# ton1.net
KiCad netlist of a schematic drawn in EAGLE
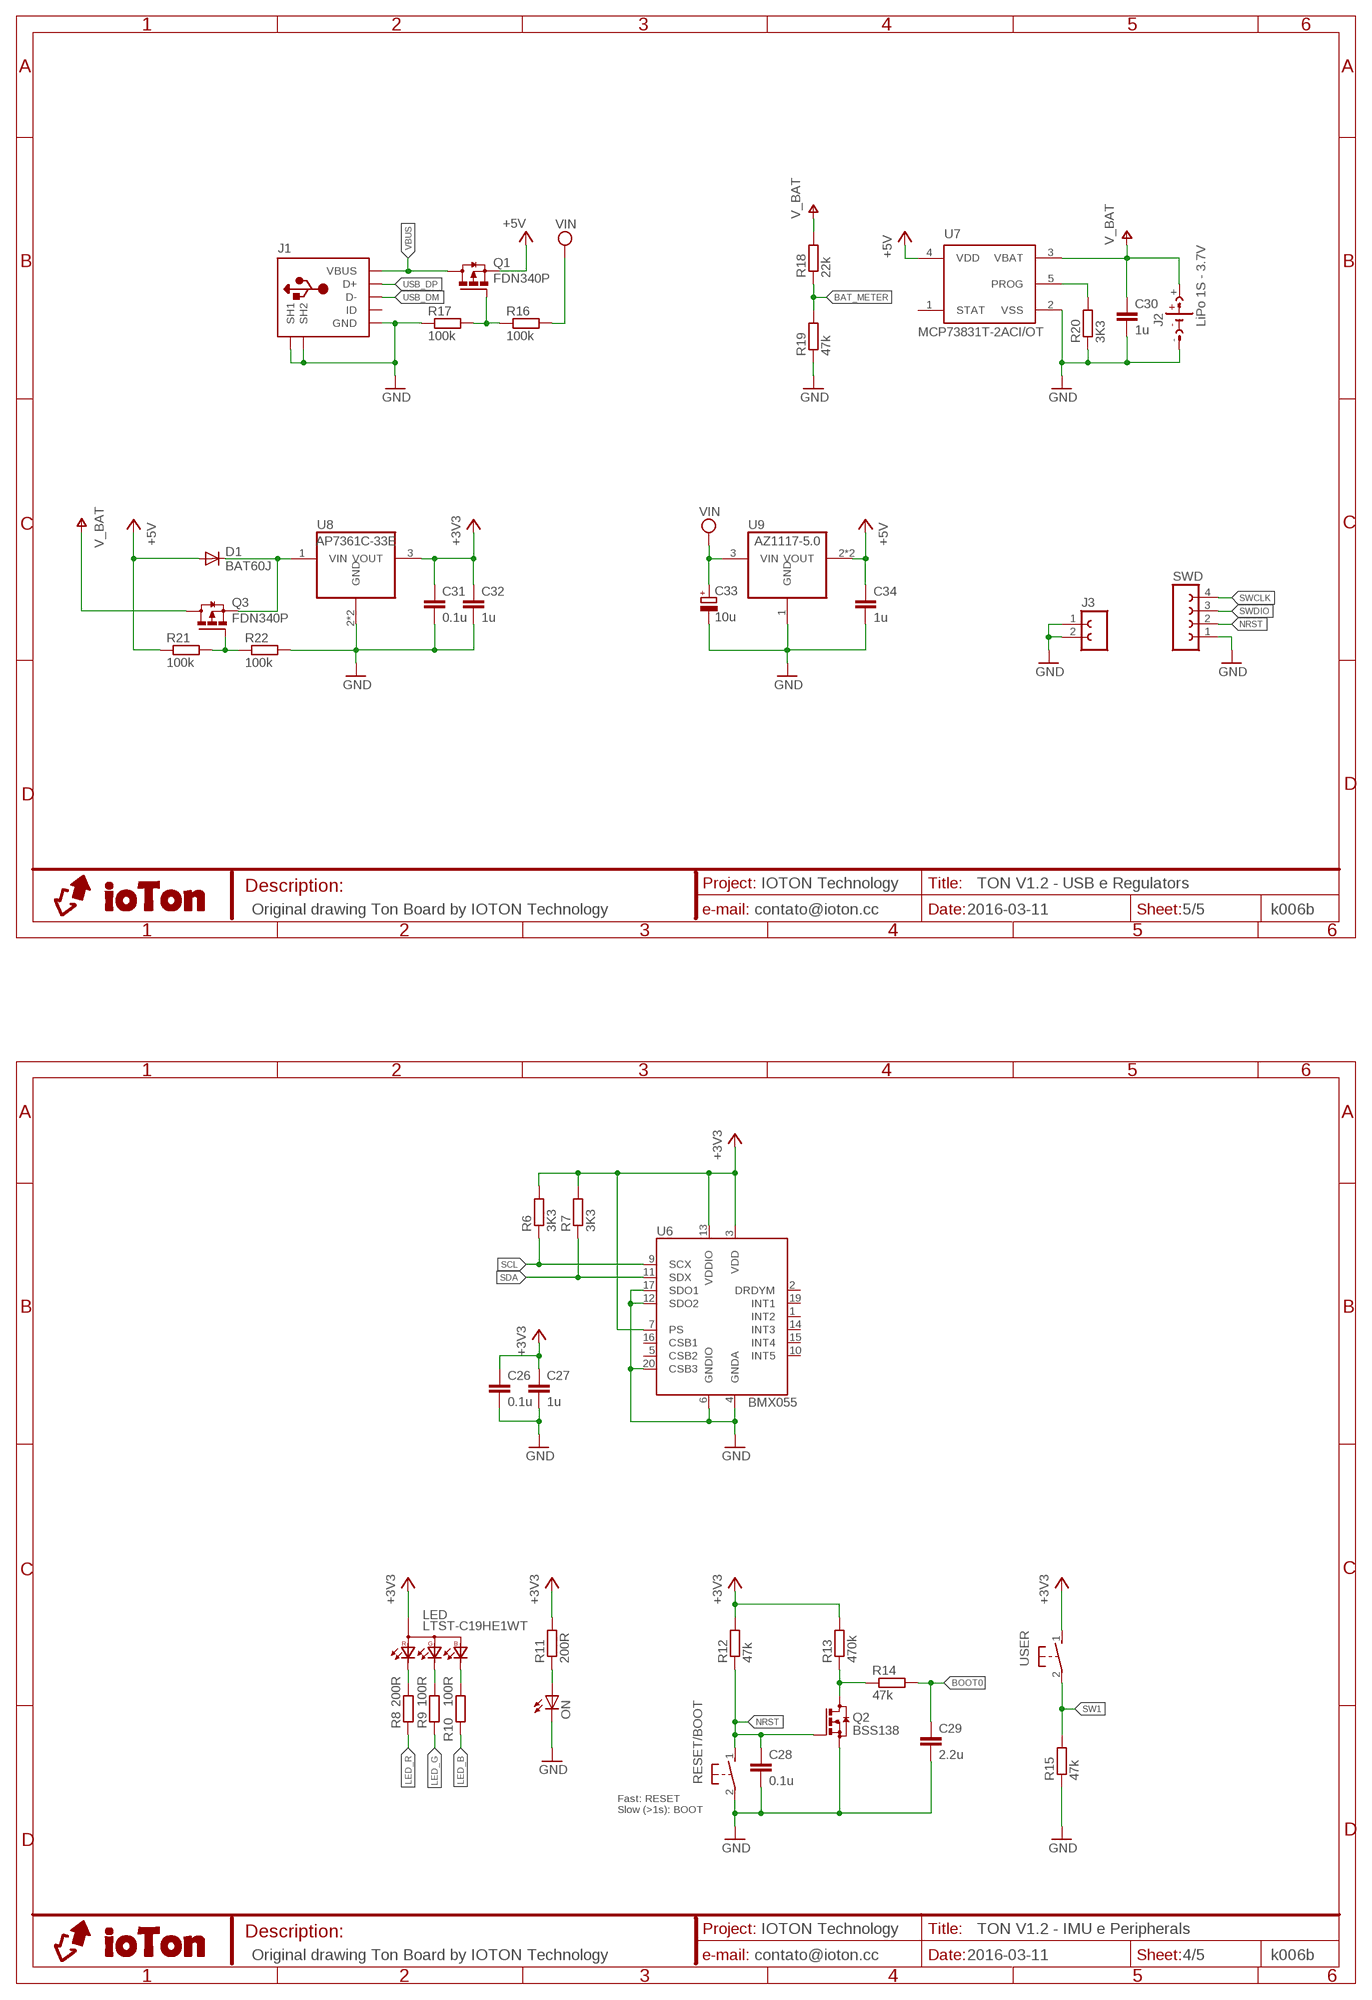
[diagram p0: schematic, sheet 1, part 1 of 3]
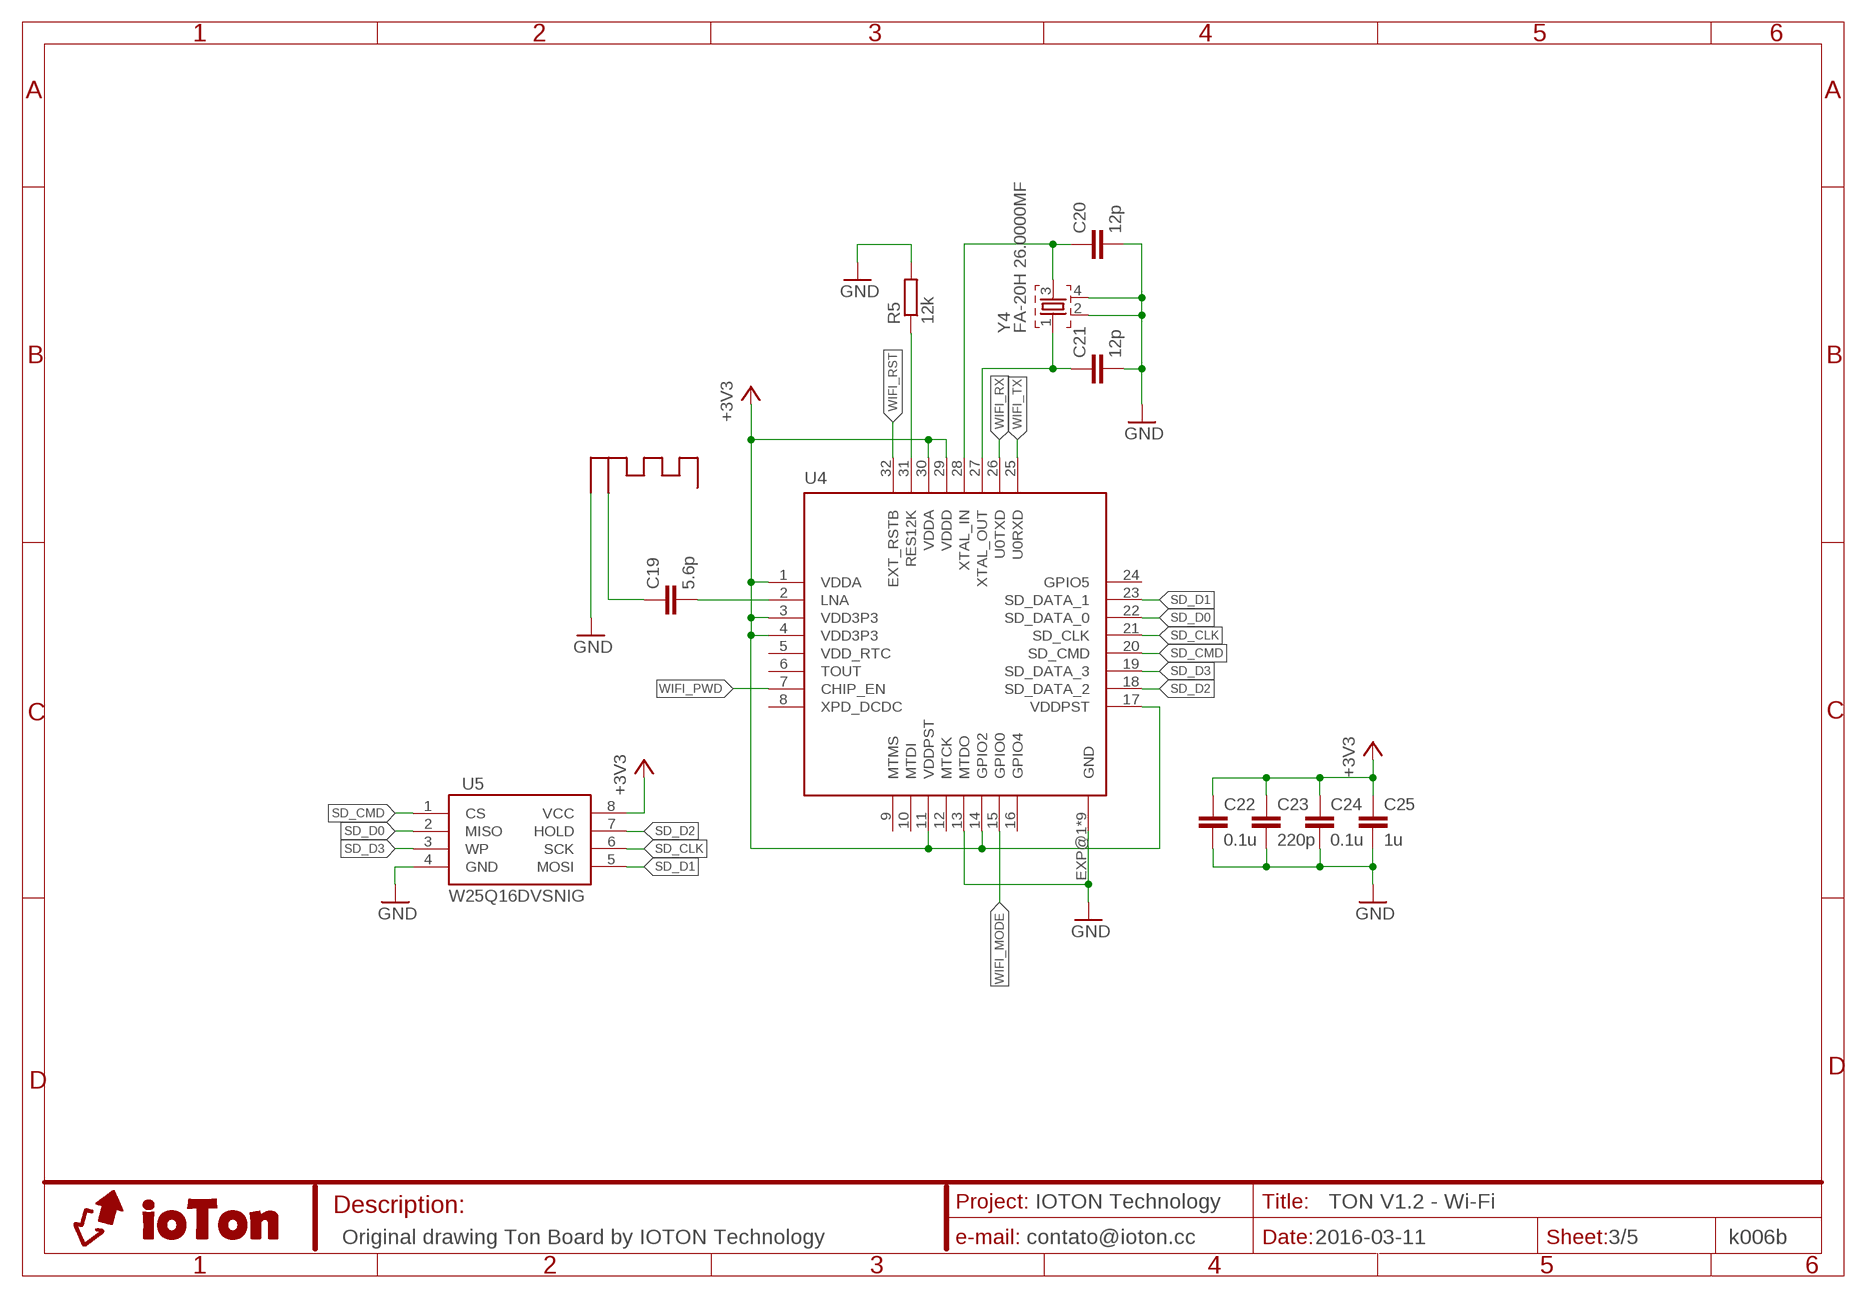
[diagram p1: schematic, sheet 1, part 2 of 3]
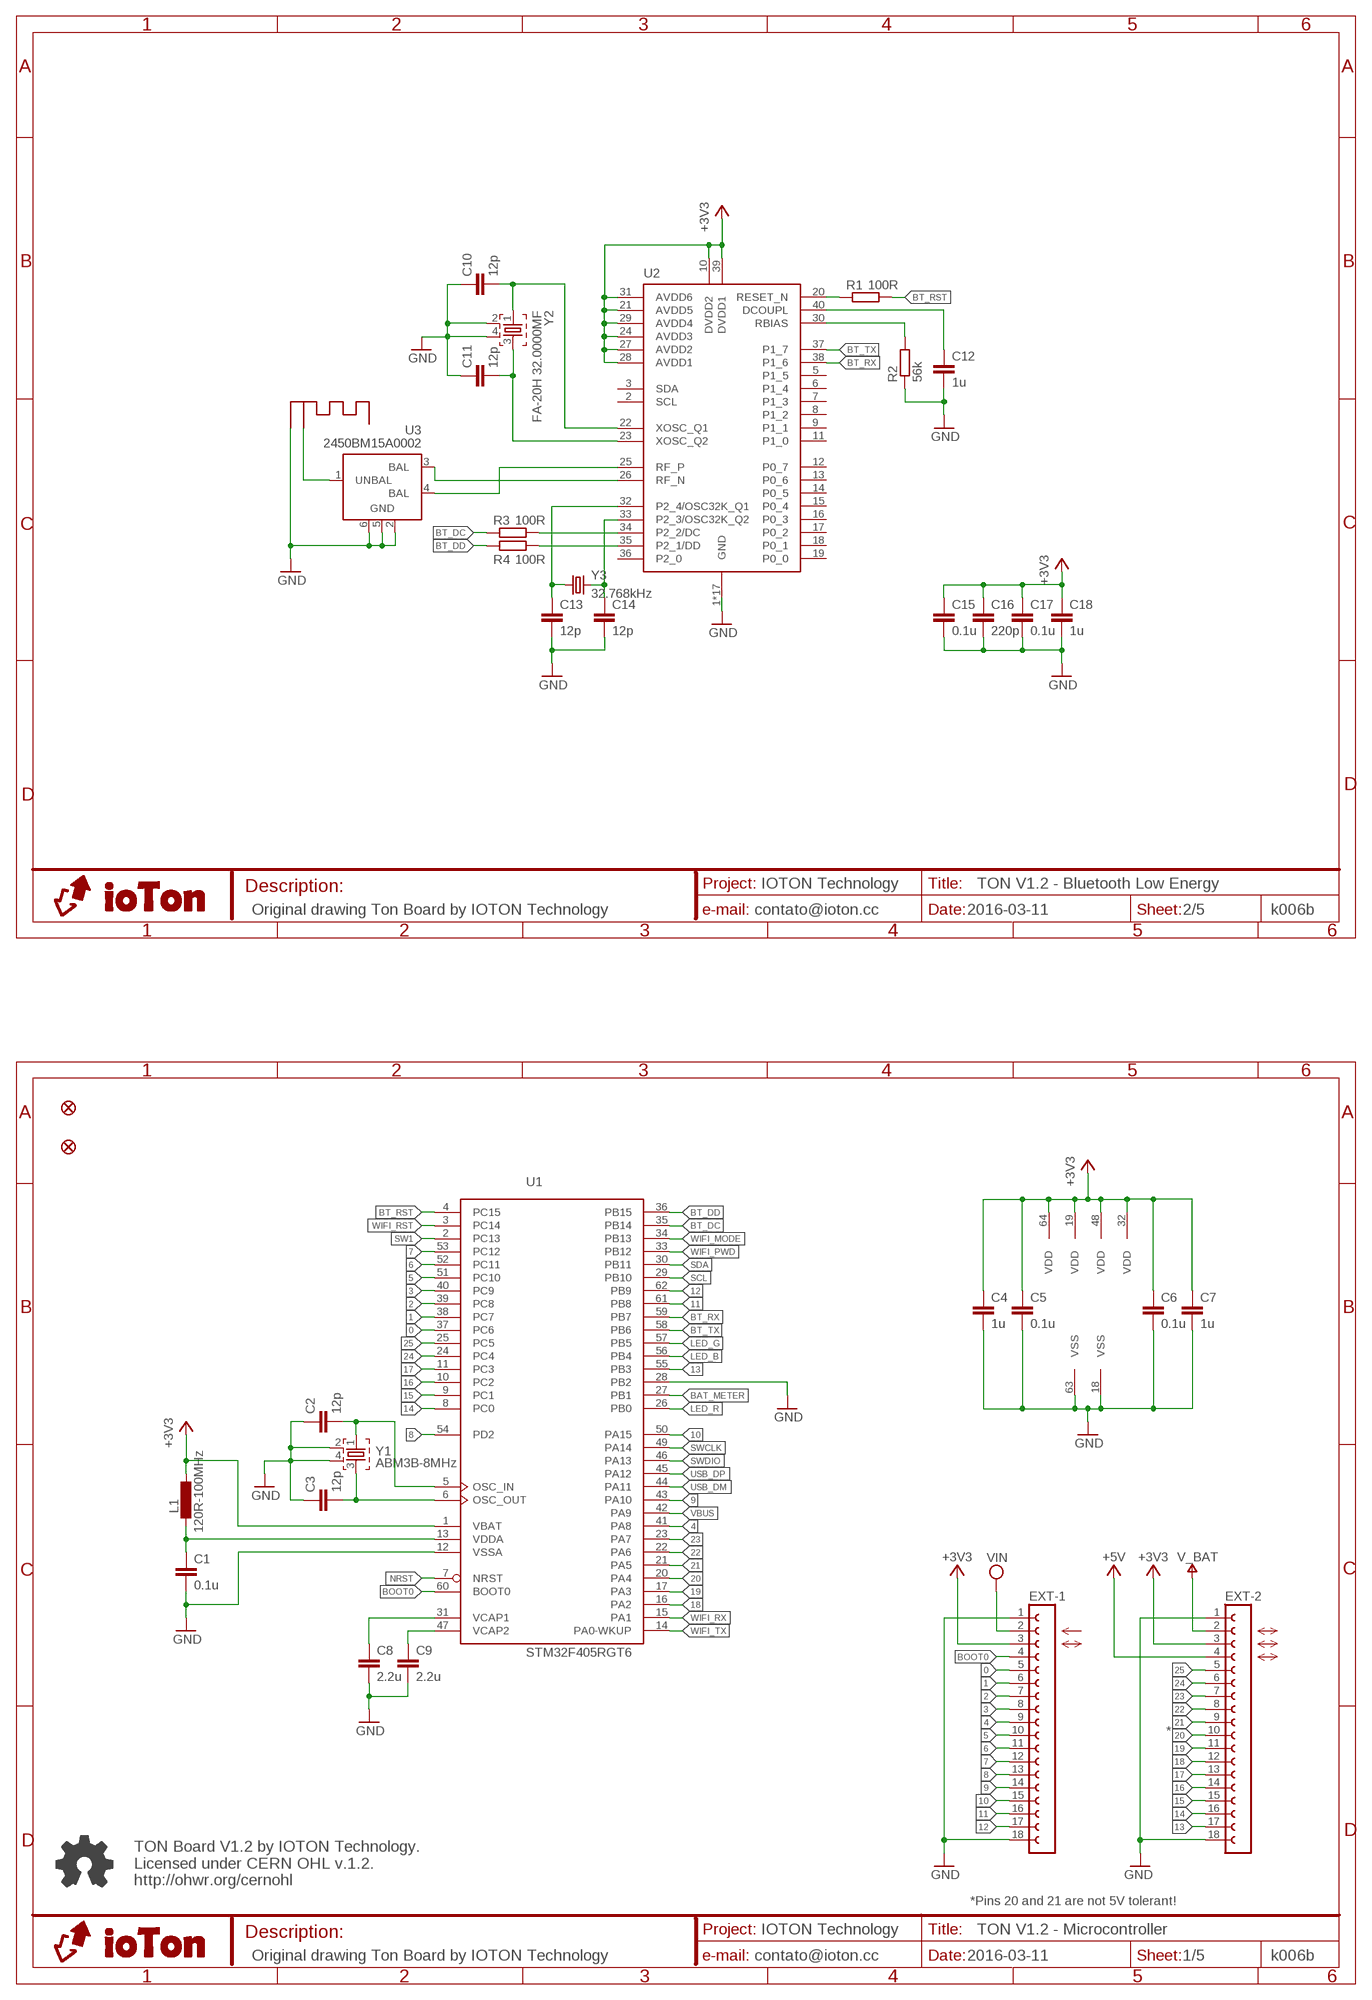
[diagram p2: schematic, sheet 1, part 3 of 3]

(export (version "E")
  (design (tool "Eeschema 10.0.6"))
  (components
    (comp (ref "C1")
      (value "0.1u")
      (footprint "eagle-import:C0603")
      (libsource (lib "eagle-import") (part "C-EUC0603"))
    )
    (comp (ref "C2")
      (value "12p")
      (footprint "eagle-import:C0402")
      (libsource (lib "eagle-import") (part "C-EUC0402"))
    )
    (comp (ref "C3")
      (value "12p")
      (footprint "eagle-import:C0402")
      (libsource (lib "eagle-import") (part "C-EUC0402"))
    )
    (comp (ref "C4")
      (value "1u")
      (footprint "eagle-import:C0603")
      (libsource (lib "eagle-import") (part "C-EUC0603"))
    )
    (comp (ref "C5")
      (value "0.1u")
      (footprint "eagle-import:C0603")
      (libsource (lib "eagle-import") (part "C-EUC0603"))
    )
    (comp (ref "C6")
      (value "0.1u")
      (footprint "eagle-import:C0603")
      (libsource (lib "eagle-import") (part "C-EUC0603"))
    )
    (comp (ref "C7")
      (value "1u")
      (footprint "eagle-import:C0603")
      (libsource (lib "eagle-import") (part "C-EUC0603"))
    )
    (comp (ref "C8")
      (value "2.2u")
      (footprint "eagle-import:C0603")
      (libsource (lib "eagle-import") (part "C-EUC0603"))
    )
    (comp (ref "C9")
      (value "2.2u")
      (footprint "eagle-import:C0603")
      (libsource (lib "eagle-import") (part "C-EUC0603"))
    )
    (comp (ref "C10")
      (value "12p")
      (footprint "eagle-import:C0402")
      (libsource (lib "eagle-import") (part "C-EUC0402"))
    )
    (comp (ref "C11")
      (value "12p")
      (footprint "eagle-import:C0402")
      (libsource (lib "eagle-import") (part "C-EUC0402"))
    )
    (comp (ref "C12")
      (value "1u")
      (footprint "eagle-import:C0402")
      (libsource (lib "eagle-import") (part "C-EUC0402"))
    )
    (comp (ref "C13")
      (value "12p")
      (footprint "eagle-import:C0402")
      (libsource (lib "eagle-import") (part "C-EUC0402"))
    )
    (comp (ref "C14")
      (value "12p")
      (footprint "eagle-import:C0402")
      (libsource (lib "eagle-import") (part "C-EUC0402"))
    )
    (comp (ref "C15")
      (value "0.1u")
      (footprint "eagle-import:C0402")
      (libsource (lib "eagle-import") (part "C-EUC0402"))
    )
    (comp (ref "C16")
      (value "220p")
      (footprint "eagle-import:C0402")
      (libsource (lib "eagle-import") (part "C-EUC0402"))
    )
    (comp (ref "C17")
      (value "0.1u")
      (footprint "eagle-import:C0402")
      (libsource (lib "eagle-import") (part "C-EUC0402"))
    )
    (comp (ref "C18")
      (value "1u")
      (footprint "eagle-import:C0402")
      (libsource (lib "eagle-import") (part "C-EUC0402"))
    )
    (comp (ref "C19")
      (value "5.6p")
      (footprint "eagle-import:C0402")
      (libsource (lib "eagle-import") (part "C-EUC0402"))
    )
    (comp (ref "C20")
      (value "12p")
      (footprint "eagle-import:C0402")
      (libsource (lib "eagle-import") (part "C-EUC0402"))
    )
    (comp (ref "C21")
      (value "12p")
      (footprint "eagle-import:C0402")
      (libsource (lib "eagle-import") (part "C-EUC0402"))
    )
    (comp (ref "C22")
      (value "0.1u")
      (footprint "eagle-import:C0402")
      (libsource (lib "eagle-import") (part "C-EUC0402"))
    )
    (comp (ref "C23")
      (value "220p")
      (footprint "eagle-import:C0402")
      (libsource (lib "eagle-import") (part "C-EUC0402"))
    )
    (comp (ref "C24")
      (value "0.1u")
      (footprint "eagle-import:C0402")
      (libsource (lib "eagle-import") (part "C-EUC0402"))
    )
    (comp (ref "C25")
      (value "1u")
      (footprint "eagle-import:C0402")
      (libsource (lib "eagle-import") (part "C-EUC0402"))
    )
    (comp (ref "C26")
      (value "0.1u")
      (footprint "eagle-import:C0603")
      (libsource (lib "eagle-import") (part "C-EUC0603"))
    )
    (comp (ref "C27")
      (value "1u")
      (footprint "eagle-import:C0603")
      (libsource (lib "eagle-import") (part "C-EUC0603"))
    )
    (comp (ref "C28")
      (value "0.1u")
      (footprint "eagle-import:C0603")
      (libsource (lib "eagle-import") (part "C-EUC0603"))
    )
    (comp (ref "C29")
      (value "2.2u")
      (footprint "eagle-import:C0603")
      (libsource (lib "eagle-import") (part "C-EUC0603"))
    )
    (comp (ref "C30")
      (value "1u")
      (footprint "eagle-import:C0603")
      (libsource (lib "eagle-import") (part "C-EUC0603"))
    )
    (comp (ref "C31")
      (value "0.1u")
      (footprint "eagle-import:C0603")
      (libsource (lib "eagle-import") (part "C-EUC0603"))
    )
    (comp (ref "C32")
      (value "1u")
      (footprint "eagle-import:C0603")
      (libsource (lib "eagle-import") (part "C-EUC0603"))
    )
    (comp (ref "C33")
      (value "10u")
      (footprint "eagle-import:SMC_A")
      (libsource (lib "eagle-import") (part "CPOL-EUSMCA"))
    )
    (comp (ref "C34")
      (value "1u")
      (footprint "eagle-import:C0603")
      (libsource (lib "eagle-import") (part "C-EUC0603"))
    )
    (comp (ref "D1")
      (value "BAT60J")
      (footprint "eagle-import:SOD323-R")
      (libsource (lib "eagle-import") (part "DIODE-SOD323-R"))
    )
    (comp (ref "EXT-1")
      (value "1_18")
      (footprint "eagle-import:1_18")
      (libsource (lib "eagle-import") (part "1_18"))
    )
    (comp (ref "EXT-2")
      (value "1_18")
      (footprint "eagle-import:1_18")
      (libsource (lib "eagle-import") (part "1_18"))
    )
    (comp (ref "J1")
      (value "USBR")
      (footprint "eagle-import:0475890001")
      (libsource (lib "eagle-import") (part "USBR"))
    )
    (comp (ref "J2")
      (value "LiPo 1S - 3.7V")
      (footprint "eagle-import:BATTERY")
      (libsource (lib "eagle-import") (part "BATTERY"))
    )
    (comp (ref "J3")
      (value "1_2")
      (footprint "eagle-import:1_2")
      (libsource (lib "eagle-import") (part "1_2"))
    )
    (comp (ref "JP1")
      (value "FIDUCIAL1X2")
      (footprint "eagle-import:FIDUCIAL-1X2")
      (libsource (lib "eagle-import") (part "FIDUCIAL1X2"))
    )
    (comp (ref "JP2")
      (value "FIDUCIAL1X2")
      (footprint "eagle-import:FIDUCIAL-1X2")
      (libsource (lib "eagle-import") (part "FIDUCIAL1X2"))
    )
    (comp (ref "L1")
      (value "120R-100MHz")
      (footprint "eagle-import:LR0603")
      (libsource (lib "eagle-import") (part "L-EULR0603"))
    )
    (comp (ref "LED")
      (value "LTST-C19HE1WT")
      (footprint "eagle-import:0606")
      (libsource (lib "eagle-import") (part "LED-RGB-AC"))
    )
    (comp (ref "ON")
      (value "LEDCHIPLED_0603")
      (footprint "eagle-import:CHIPLED_0603")
      (libsource (lib "eagle-import") (part "LEDCHIPLED_0603"))
    )
    (comp (ref "Q1")
      (value "FDN340P")
      (footprint "eagle-import:SUPER-SOT3")
      (libsource (lib "eagle-import") (part "FDN360P"))
    )
    (comp (ref "Q2")
      (value "BSS138")
      (footprint "eagle-import:SOT23")
      (libsource (lib "eagle-import") (part "BSS123"))
    )
    (comp (ref "Q3")
      (value "FDN340P")
      (footprint "eagle-import:SUPER-SOT3")
      (libsource (lib "eagle-import") (part "FDN360P"))
    )
    (comp (ref "R1")
      (value "100R")
      (footprint "eagle-import:R0402")
      (libsource (lib "eagle-import") (part "R-EU_R0402"))
    )
    (comp (ref "R2")
      (value "56k")
      (footprint "eagle-import:R0402")
      (libsource (lib "eagle-import") (part "R-EU_R0402"))
    )
    (comp (ref "R3")
      (value "100R")
      (footprint "eagle-import:R0402")
      (libsource (lib "eagle-import") (part "R-EU_R0402"))
    )
    (comp (ref "R4")
      (value "100R")
      (footprint "eagle-import:R0402")
      (libsource (lib "eagle-import") (part "R-EU_R0402"))
    )
    (comp (ref "R5")
      (value "12k")
      (footprint "eagle-import:R0402")
      (libsource (lib "eagle-import") (part "R-EU_R0402"))
    )
    (comp (ref "R6")
      (value "3K3")
      (footprint "eagle-import:R0603")
      (libsource (lib "eagle-import") (part "R-EU_R0603"))
    )
    (comp (ref "R7")
      (value "3K3")
      (footprint "eagle-import:R0603")
      (libsource (lib "eagle-import") (part "R-EU_R0603"))
    )
    (comp (ref "R8")
      (value "200R")
      (footprint "eagle-import:R0603")
      (libsource (lib "eagle-import") (part "R-EU_R0603"))
    )
    (comp (ref "R9")
      (value "100R")
      (footprint "eagle-import:R0603")
      (libsource (lib "eagle-import") (part "R-EU_R0603"))
    )
    (comp (ref "R10")
      (value "100R")
      (footprint "eagle-import:R0603")
      (libsource (lib "eagle-import") (part "R-EU_R0603"))
    )
    (comp (ref "R11")
      (value "200R")
      (footprint "eagle-import:R0603")
      (libsource (lib "eagle-import") (part "R-EU_R0603"))
    )
    (comp (ref "R12")
      (value "47k")
      (footprint "eagle-import:R0603")
      (libsource (lib "eagle-import") (part "R-EU_R0603"))
    )
    (comp (ref "R13")
      (value "470k")
      (footprint "eagle-import:R0603")
      (libsource (lib "eagle-import") (part "R-EU_R0603"))
    )
    (comp (ref "R14")
      (value "47k")
      (footprint "eagle-import:R0603")
      (libsource (lib "eagle-import") (part "R-EU_R0603"))
    )
    (comp (ref "R15")
      (value "47k")
      (footprint "eagle-import:R0603")
      (libsource (lib "eagle-import") (part "R-EU_R0603"))
    )
    (comp (ref "R16")
      (value "100k")
      (footprint "eagle-import:R0603")
      (libsource (lib "eagle-import") (part "R-EU_R0603"))
    )
    (comp (ref "R17")
      (value "100k")
      (footprint "eagle-import:R0603")
      (libsource (lib "eagle-import") (part "R-EU_R0603"))
    )
    (comp (ref "R18")
      (value "22k")
      (footprint "eagle-import:R0603")
      (libsource (lib "eagle-import") (part "R-EU_R0603"))
    )
    (comp (ref "R19")
      (value "47k")
      (footprint "eagle-import:R0603")
      (libsource (lib "eagle-import") (part "R-EU_R0603"))
    )
    (comp (ref "R20")
      (value "3K3")
      (footprint "eagle-import:R0603")
      (libsource (lib "eagle-import") (part "R-EU_R0603"))
    )
    (comp (ref "R21")
      (value "100k")
      (footprint "eagle-import:R0603")
      (libsource (lib "eagle-import") (part "R-EU_R0603"))
    )
    (comp (ref "R22")
      (value "100k")
      (footprint "eagle-import:R0603")
      (libsource (lib "eagle-import") (part "R-EU_R0603"))
    )
    (comp (ref "RESET/BOOT")
      (value "SWITCH")
      (footprint "eagle-import:SW_TL-3330")
      (libsource (lib "eagle-import") (part "SWITCH"))
    )
    (comp (ref "SWD")
      (value "FE04-11")
      (footprint "eagle-import:CON4-1_1")
      (libsource (lib "eagle-import") (part "FE04-11"))
    )
    (comp (ref "U$1")
      (value "ANT_PCBR")
      (footprint "eagle-import:ANT_MIFA_R")
      (libsource (lib "eagle-import") (part "ANT_PCBR"))
    )
    (comp (ref "U$2")
      (value "ANT_PCBL")
      (footprint "eagle-import:ANT_MIFA_L")
      (libsource (lib "eagle-import") (part "ANT_PCBL"))
    )
    (comp (ref "U1")
      (value "STM32F405RGT6")
      (footprint "eagle-import:LQFP64")
      (libsource (lib "eagle-import") (part "STM32F405RTG"))
    )
    (comp (ref "U2")
      (value "CC2541")
      (footprint "eagle-import:QFN40-6X6")
      (libsource (lib "eagle-import") (part "CC2541"))
    )
    (comp (ref "U3")
      (value "2450BM15A0002")
      (footprint "eagle-import:2450BM15A0002")
      (libsource (lib "eagle-import") (part "2450BM15A0002"))
    )
    (comp (ref "U4")
      (value "ESP8266O")
      (footprint "eagle-import:QFN32-5X5-O")
      (libsource (lib "eagle-import") (part "ESP8266O"))
    )
    (comp (ref "U5")
      (value "W25Q16DVSNIG")
      (footprint "eagle-import:SO08")
      (libsource (lib "eagle-import") (part "SPI_FLASH-X25XXSMD"))
    )
    (comp (ref "U6")
      (value "BMX055")
      (footprint "eagle-import:LGA20-4.5X3")
      (libsource (lib "eagle-import") (part "BMX055"))
    )
    (comp (ref "U7")
      (value "MCP73831T-2ACI/OT")
      (footprint "eagle-import:SOT23-5L")
      (libsource (lib "eagle-import") (part "MCP73831/OT"))
    )
    (comp (ref "U8")
      (value "AP7361C-33E")
      (footprint "eagle-import:SOT223")
      (libsource (lib "eagle-import") (part "LDO-IGO"))
    )
    (comp (ref "U9")
      (value "AZ1117-5.0")
      (footprint "eagle-import:SOT223")
      (fields (field (name "MPN") "REG1117"))
      (libsource (lib "eagle-import") (part "LM1117"))
    )
    (comp (ref "USER")
      (value "SWITCH")
      (footprint "eagle-import:SW_TL-3330")
      (libsource (lib "eagle-import") (part "SWITCH"))
    )
    (comp (ref "Y1")
      (value "ABM3B-8MHz")
      (footprint "eagle-import:ABM3B")
      (libsource (lib "eagle-import") (part "FA-ABM3B"))
    )
    (comp (ref "Y2")
      (value "FA-20H 32.0000MF")
      (footprint "eagle-import:FA-20H")
      (libsource (lib "eagle-import") (part "FA-20H"))
    )
    (comp (ref "Y3")
      (value "32.768kHz")
      (footprint "eagle-import:3.2X1.5")
      (libsource (lib "eagle-import") (part "CRYSTAL_32.768K"))
    )
    (comp (ref "Y4")
      (value "FA-20H 26.0000MF")
      (footprint "eagle-import:FA-20H")
      (libsource (lib "eagle-import") (part "FA-20H"))
    )
  )
  (nets
    (net (code "1") (name "+3V3") (class "Default")
      (node (ref "C15") (pin "1") (pinfunction "1_1") (pintype "passive"))
      (node (ref "C16") (pin "1") (pinfunction "1_1") (pintype "passive"))
      (node (ref "C17") (pin "1") (pinfunction "1_1") (pintype "passive"))
      (node (ref "C18") (pin "1") (pinfunction "1_1") (pintype "passive"))
      (node (ref "C22") (pin "1") (pinfunction "1_1") (pintype "passive"))
      (node (ref "C23") (pin "1") (pinfunction "1_1") (pintype "passive"))
      (node (ref "C24") (pin "1") (pinfunction "1_1") (pintype "passive"))
      (node (ref "C25") (pin "1") (pinfunction "1_1") (pintype "passive"))
      (node (ref "C26") (pin "1") (pinfunction "1_1") (pintype "passive"))
      (node (ref "C27") (pin "1") (pinfunction "1_1") (pintype "passive"))
      (node (ref "C31") (pin "1") (pinfunction "1_1") (pintype "passive"))
      (node (ref "C32") (pin "1") (pinfunction "1_1") (pintype "passive"))
      (node (ref "C4") (pin "1") (pinfunction "1_1") (pintype "passive"))
      (node (ref "C5") (pin "1") (pinfunction "1_1") (pintype "passive"))
      (node (ref "C6") (pin "1") (pinfunction "1_1") (pintype "passive"))
      (node (ref "C7") (pin "1") (pinfunction "1_1") (pintype "passive"))
      (node (ref "EXT-1") (pin "3") (pinfunction "3_3") (pintype "passive"))
      (node (ref "EXT-2") (pin "3") (pinfunction "3_3") (pintype "passive"))
      (node (ref "L1") (pin "2") (pinfunction "2_2") (pintype "passive"))
      (node (ref "LED") (pin "4") (pinfunction "A_4") (pintype "passive"))
      (node (ref "R11") (pin "2") (pinfunction "2_2") (pintype "passive"))
      (node (ref "R12") (pin "2") (pinfunction "2_2") (pintype "passive"))
      (node (ref "R13") (pin "2") (pinfunction "2_2") (pintype "passive"))
      (node (ref "R6") (pin "2") (pinfunction "2_2") (pintype "passive"))
      (node (ref "R7") (pin "2") (pinfunction "2_2") (pintype "passive"))
      (node (ref "U1") (pin "1") (pinfunction "VBAT_1") (pintype "power_in"))
      (node (ref "U1") (pin "19") (pinfunction "VDD_19") (pintype "power_in"))
      (node (ref "U1") (pin "32") (pinfunction "VDD_32") (pintype "power_in"))
      (node (ref "U1") (pin "48") (pinfunction "VDD_48") (pintype "power_in"))
      (node (ref "U1") (pin "64") (pinfunction "VDD_64") (pintype "power_in"))
      (node (ref "U2") (pin "10") (pinfunction "DVDD2_10") (pintype "power_in"))
      (node (ref "U2") (pin "21") (pinfunction "AVDD5_21") (pintype "power_in"))
      (node (ref "U2") (pin "24") (pinfunction "AVDD3_24") (pintype "power_in"))
      (node (ref "U2") (pin "27") (pinfunction "AVDD2_27") (pintype "power_in"))
      (node (ref "U2") (pin "28") (pinfunction "AVDD1_28") (pintype "power_in"))
      (node (ref "U2") (pin "29") (pinfunction "AVDD4_29") (pintype "power_in"))
      (node (ref "U2") (pin "31") (pinfunction "AVDD6_31") (pintype "power_in"))
      (node (ref "U2") (pin "39") (pinfunction "DVDD1_39") (pintype "power_in"))
      (node (ref "U4") (pin "1") (pinfunction "VDDA_1") (pintype "power_in"))
      (node (ref "U4") (pin "11") (pinfunction "VDDPST_11") (pintype "power_in"))
      (node (ref "U4") (pin "14") (pinfunction "GPIO2_14") (pintype "bidirectional"))
      (node (ref "U4") (pin "17") (pinfunction "VDDPST_17") (pintype "power_in"))
      (node (ref "U4") (pin "29") (pinfunction "VDDD_29") (pintype "power_in"))
      (node (ref "U4") (pin "3") (pinfunction "VDD3P3_3") (pintype "power_in"))
      (node (ref "U4") (pin "30") (pinfunction "VDDA_30") (pintype "power_in"))
      (node (ref "U4") (pin "4") (pinfunction "VDD3P3_4") (pintype "power_in"))
      (node (ref "U5") (pin "8") (pinfunction "VCC_8") (pintype "bidirectional"))
      (node (ref "U6") (pin "13") (pinfunction "VDDIO_13") (pintype "power_in"))
      (node (ref "U6") (pin "3") (pinfunction "VDD_3") (pintype "power_in"))
      (node (ref "U6") (pin "7") (pinfunction "PS_7") (pintype "input"))
      (node (ref "U8") (pin "3") (pinfunction "VOUT_3") (pintype "output"))
      (node (ref "USER") (pin "1") (pinfunction "1_1") (pintype "passive"))
    )
    (net (code "2") (name "+5V") (class "Default")
      (node (ref "C34") (pin "1") (pinfunction "1_1") (pintype "passive"))
      (node (ref "D1") (pin "A") (pinfunction "A_A") (pintype "passive"))
      (node (ref "EXT-2") (pin "4") (pinfunction "4_4") (pintype "passive"))
      (node (ref "Q1") (pin "2") (pinfunction "S_2") (pintype "passive"))
      (node (ref "R21") (pin "1") (pinfunction "1_1") (pintype "passive"))
      (node (ref "U7") (pin "4") (pinfunction "VDD_4") (pintype "power_in"))
      (node (ref "U9") (pin "2") (pinfunction "VOUT_2") (pintype "output"))
      (node (ref "U9") (pin "4") (pinfunction "VOUT_4") (pintype "output"))
    )
    (net (code "3") (name "/VDD_RTC") (class "Default")
      (node (ref "U4") (pin "5") (pinfunction "VDD_RTC_5") (pintype "power_in"))
    )
    (net (code "4") (name "0") (class "Default")
      (node (ref "EXT-1") (pin "5") (pinfunction "5_5") (pintype "passive"))
      (node (ref "U1") (pin "37") (pinfunction "PC6_37") (pintype "bidirectional"))
    )
    (net (code "5") (name "1") (class "Default")
      (node (ref "EXT-1") (pin "6") (pinfunction "6_6") (pintype "passive"))
      (node (ref "U1") (pin "38") (pinfunction "PC7_38") (pintype "bidirectional"))
    )
    (net (code "6") (name "2") (class "Default")
      (node (ref "EXT-1") (pin "7") (pinfunction "7_7") (pintype "passive"))
      (node (ref "U1") (pin "39") (pinfunction "PC8_39") (pintype "bidirectional"))
    )
    (net (code "7") (name "3") (class "Default")
      (node (ref "EXT-1") (pin "8") (pinfunction "8_8") (pintype "passive"))
      (node (ref "U1") (pin "40") (pinfunction "PC9_40") (pintype "bidirectional"))
    )
    (net (code "8") (name "4") (class "Default")
      (node (ref "EXT-1") (pin "9") (pinfunction "9_9") (pintype "passive"))
      (node (ref "U1") (pin "41") (pinfunction "PA8_41") (pintype "bidirectional"))
    )
    (net (code "9") (name "5") (class "Default")
      (node (ref "EXT-1") (pin "10") (pinfunction "10_10") (pintype "passive"))
      (node (ref "U1") (pin "51") (pinfunction "PC10_51") (pintype "bidirectional"))
    )
    (net (code "10") (name "6") (class "Default")
      (node (ref "EXT-1") (pin "11") (pinfunction "11_11") (pintype "passive"))
      (node (ref "U1") (pin "52") (pinfunction "PC11_52") (pintype "bidirectional"))
    )
    (net (code "11") (name "7") (class "Default")
      (node (ref "EXT-1") (pin "12") (pinfunction "12_12") (pintype "passive"))
      (node (ref "U1") (pin "53") (pinfunction "PC12_53") (pintype "bidirectional"))
    )
    (net (code "12") (name "8") (class "Default")
      (node (ref "EXT-1") (pin "13") (pinfunction "13_13") (pintype "passive"))
      (node (ref "U1") (pin "54") (pinfunction "PD2_54") (pintype "bidirectional"))
    )
    (net (code "13") (name "9") (class "Default")
      (node (ref "EXT-1") (pin "14") (pinfunction "14_14") (pintype "passive"))
      (node (ref "U1") (pin "43") (pinfunction "PA10_43") (pintype "bidirectional"))
    )
    (net (code "14") (name "10") (class "Default")
      (node (ref "EXT-1") (pin "15") (pinfunction "15_15") (pintype "passive"))
      (node (ref "U1") (pin "50") (pinfunction "PA15_50") (pintype "bidirectional"))
    )
    (net (code "15") (name "11") (class "Default")
      (node (ref "EXT-1") (pin "16") (pinfunction "16_16") (pintype "passive"))
      (node (ref "U1") (pin "61") (pinfunction "PB8_61") (pintype "bidirectional"))
    )
    (net (code "16") (name "12") (class "Default")
      (node (ref "EXT-1") (pin "17") (pinfunction "17_17") (pintype "passive"))
      (node (ref "U1") (pin "62") (pinfunction "PB9_62") (pintype "bidirectional"))
    )
    (net (code "17") (name "13") (class "Default")
      (node (ref "EXT-2") (pin "17") (pinfunction "17_17") (pintype "passive"))
      (node (ref "U1") (pin "55") (pinfunction "PB3_55") (pintype "bidirectional"))
    )
    (net (code "18") (name "14") (class "Default")
      (node (ref "EXT-2") (pin "16") (pinfunction "16_16") (pintype "passive"))
      (node (ref "U1") (pin "8") (pinfunction "PC0_8") (pintype "bidirectional"))
    )
    (net (code "19") (name "15") (class "Default")
      (node (ref "EXT-2") (pin "15") (pinfunction "15_15") (pintype "passive"))
      (node (ref "U1") (pin "9") (pinfunction "PC1_9") (pintype "bidirectional"))
    )
    (net (code "20") (name "16") (class "Default")
      (node (ref "EXT-2") (pin "14") (pinfunction "14_14") (pintype "passive"))
      (node (ref "U1") (pin "10") (pinfunction "PC2_10") (pintype "bidirectional"))
    )
    (net (code "21") (name "17") (class "Default")
      (node (ref "EXT-2") (pin "13") (pinfunction "13_13") (pintype "passive"))
      (node (ref "U1") (pin "11") (pinfunction "PC3_11") (pintype "bidirectional"))
    )
    (net (code "22") (name "18") (class "Default")
      (node (ref "EXT-2") (pin "12") (pinfunction "12_12") (pintype "passive"))
      (node (ref "U1") (pin "16") (pinfunction "PA2_16") (pintype "bidirectional"))
    )
    (net (code "23") (name "19") (class "Default")
      (node (ref "EXT-2") (pin "11") (pinfunction "11_11") (pintype "passive"))
      (node (ref "U1") (pin "17") (pinfunction "PA3_17") (pintype "bidirectional"))
    )
    (net (code "24") (name "20") (class "Default")
      (node (ref "EXT-2") (pin "10") (pinfunction "10_10") (pintype "passive"))
      (node (ref "U1") (pin "20") (pinfunction "PA4_20") (pintype "bidirectional"))
    )
    (net (code "25") (name "21") (class "Default")
      (node (ref "EXT-2") (pin "9") (pinfunction "9_9") (pintype "passive"))
      (node (ref "U1") (pin "21") (pinfunction "PA5_21") (pintype "bidirectional"))
    )
    (net (code "26") (name "22") (class "Default")
      (node (ref "EXT-2") (pin "8") (pinfunction "8_8") (pintype "passive"))
      (node (ref "U1") (pin "22") (pinfunction "PA6_22") (pintype "bidirectional"))
    )
    (net (code "27") (name "23") (class "Default")
      (node (ref "EXT-2") (pin "7") (pinfunction "7_7") (pintype "passive"))
      (node (ref "U1") (pin "23") (pinfunction "PA7_23") (pintype "bidirectional"))
    )
    (net (code "28") (name "24") (class "Default")
      (node (ref "EXT-2") (pin "6") (pinfunction "6_6") (pintype "passive"))
      (node (ref "U1") (pin "24") (pinfunction "PC4_24") (pintype "bidirectional"))
    )
    (net (code "29") (name "25") (class "Default")
      (node (ref "EXT-2") (pin "5") (pinfunction "5_5") (pintype "passive"))
      (node (ref "U1") (pin "25") (pinfunction "PC5_25") (pintype "bidirectional"))
    )
    (net (code "30") (name "BAT_METER") (class "Default")
      (node (ref "R18") (pin "1") (pinfunction "1_1") (pintype "passive"))
      (node (ref "R19") (pin "2") (pinfunction "2_2") (pintype "passive"))
      (node (ref "U1") (pin "27") (pinfunction "PB1_27") (pintype "bidirectional"))
    )
    (net (code "31") (name "BOOT0") (class "Default")
      (node (ref "C29") (pin "1") (pinfunction "1_1") (pintype "passive"))
      (node (ref "EXT-1") (pin "4") (pinfunction "4_4") (pintype "passive"))
      (node (ref "R14") (pin "2") (pinfunction "2_2") (pintype "passive"))
      (node (ref "U1") (pin "60") (pinfunction "BOOT0_60") (pintype "input"))
    )
    (net (code "32") (name "BT_DC") (class "Default")
      (node (ref "R3") (pin "1") (pinfunction "1_1") (pintype "passive"))
      (node (ref "U1") (pin "35") (pinfunction "PB14_35") (pintype "bidirectional"))
    )
    (net (code "33") (name "BT_DD") (class "Default")
      (node (ref "R4") (pin "1") (pinfunction "1_1") (pintype "passive"))
      (node (ref "U1") (pin "36") (pinfunction "PB15_36") (pintype "bidirectional"))
    )
    (net (code "34") (name "BT_RST") (class "Default")
      (node (ref "R1") (pin "2") (pinfunction "2_2") (pintype "passive"))
      (node (ref "U1") (pin "4") (pinfunction "PC15_4") (pintype "bidirectional"))
    )
    (net (code "35") (name "BT_RX") (class "Default")
      (node (ref "U1") (pin "59") (pinfunction "PB7_59") (pintype "bidirectional"))
      (node (ref "U2") (pin "38") (pinfunction "P1_6_38") (pintype "bidirectional"))
    )
    (net (code "36") (name "BT_TX") (class "Default")
      (node (ref "U1") (pin "58") (pinfunction "PB6_58") (pintype "bidirectional"))
      (node (ref "U2") (pin "37") (pinfunction "P1_7_37") (pintype "bidirectional"))
    )
    (net (code "37") (name "GND") (class "Default")
      (node (ref "C1") (pin "2") (pinfunction "2_2") (pintype "passive"))
      (node (ref "C10") (pin "1") (pinfunction "1_1") (pintype "passive"))
      (node (ref "C11") (pin "1") (pinfunction "1_1") (pintype "passive"))
      (node (ref "C12") (pin "2") (pinfunction "2_2") (pintype "passive"))
      (node (ref "C13") (pin "2") (pinfunction "2_2") (pintype "passive"))
      (node (ref "C14") (pin "2") (pinfunction "2_2") (pintype "passive"))
      (node (ref "C15") (pin "2") (pinfunction "2_2") (pintype "passive"))
      (node (ref "C16") (pin "2") (pinfunction "2_2") (pintype "passive"))
      (node (ref "C17") (pin "2") (pinfunction "2_2") (pintype "passive"))
      (node (ref "C18") (pin "2") (pinfunction "2_2") (pintype "passive"))
      (node (ref "C2") (pin "1") (pinfunction "1_1") (pintype "passive"))
      (node (ref "C20") (pin "2") (pinfunction "2_2") (pintype "passive"))
      (node (ref "C21") (pin "2") (pinfunction "2_2") (pintype "passive"))
      (node (ref "C22") (pin "2") (pinfunction "2_2") (pintype "passive"))
      (node (ref "C23") (pin "2") (pinfunction "2_2") (pintype "passive"))
      (node (ref "C24") (pin "2") (pinfunction "2_2") (pintype "passive"))
      (node (ref "C25") (pin "2") (pinfunction "2_2") (pintype "passive"))
      (node (ref "C26") (pin "2") (pinfunction "2_2") (pintype "passive"))
      (node (ref "C27") (pin "2") (pinfunction "2_2") (pintype "passive"))
      (node (ref "C28") (pin "2") (pinfunction "2_2") (pintype "passive"))
      (node (ref "C29") (pin "2") (pinfunction "2_2") (pintype "passive"))
      (node (ref "C3") (pin "1") (pinfunction "1_1") (pintype "passive"))
      (node (ref "C30") (pin "2") (pinfunction "2_2") (pintype "passive"))
      (node (ref "C31") (pin "2") (pinfunction "2_2") (pintype "passive"))
      (node (ref "C32") (pin "2") (pinfunction "2_2") (pintype "passive"))
      (node (ref "C33") (pin "-") (pinfunction "-_-") (pintype "passive"))
      (node (ref "C34") (pin "2") (pinfunction "2_2") (pintype "passive"))
      (node (ref "C4") (pin "2") (pinfunction "2_2") (pintype "passive"))
      (node (ref "C5") (pin "2") (pinfunction "2_2") (pintype "passive"))
      (node (ref "C6") (pin "2") (pinfunction "2_2") (pintype "passive"))
      (node (ref "C7") (pin "2") (pinfunction "2_2") (pintype "passive"))
      (node (ref "C8") (pin "2") (pinfunction "2_2") (pintype "passive"))
      (node (ref "C9") (pin "2") (pinfunction "2_2") (pintype "passive"))
      (node (ref "EXT-1") (pin "1") (pinfunction "1_1") (pintype "passive"))
      (node (ref "EXT-1") (pin "18") (pinfunction "18_18") (pintype "passive"))
      (node (ref "EXT-2") (pin "1") (pinfunction "1_1") (pintype "passive"))
      (node (ref "EXT-2") (pin "18") (pinfunction "18_18") (pintype "passive"))
      (node (ref "J1") (pin "5") (pinfunction "GND_5") (pintype "power_in"))
      (node (ref "J1") (pin "SH1") (pinfunction "SH1_SH1") (pintype "passive"))
      (node (ref "J1") (pin "SH2") (pinfunction "SH1_SH2") (pintype "passive"))
      (node (ref "J1") (pin "SH3") (pinfunction "SH2_SH3") (pintype "passive"))
      (node (ref "J1") (pin "SH4") (pinfunction "SH2_SH4") (pintype "passive"))
      (node (ref "J1") (pin "SH5") (pinfunction "SH1_SH5") (pintype "passive"))
      (node (ref "J1") (pin "SH6") (pinfunction "SH2_SH6") (pintype "passive"))
      (node (ref "J2") (pin "-") (pinfunction "-_-") (pintype "passive"))
      (node (ref "J3") (pin "1") (pinfunction "1_1") (pintype "passive"))
      (node (ref "J3") (pin "2") (pinfunction "2_2") (pintype "passive"))
      (node (ref "ON") (pin "C") (pinfunction "C_C") (pintype "passive"))
      (node (ref "Q2") (pin "2") (pinfunction "S_2") (pintype "passive"))
      (node (ref "R15") (pin "1") (pinfunction "1_1") (pintype "passive"))
      (node (ref "R17") (pin "1") (pinfunction "1_1") (pintype "passive"))
      (node (ref "R19") (pin "1") (pinfunction "1_1") (pintype "passive"))
      (node (ref "R2") (pin "1") (pinfunction "1_1") (pintype "passive"))
      (node (ref "R20") (pin "1") (pinfunction "1_1") (pintype "passive"))
      (node (ref "R22") (pin "2") (pinfunction "2_2") (pintype "passive"))
      (node (ref "R5") (pin "2") (pinfunction "2_2") (pintype "passive"))
      (node (ref "RESET/BOOT") (pin "2") (pinfunction "2_2") (pintype "passive"))
      (node (ref "SWD") (pin "1") (pinfunction "1_1") (pintype "passive"))
      (node (ref "U$1") (pin "GND") (pinfunction "GND_GND") (pintype "passive"))
      (node (ref "U$2") (pin "GND") (pinfunction "GND_GND") (pintype "passive"))
      (node (ref "U1") (pin "12") (pinfunction "VSSA_12") (pintype "power_in"))
      (node (ref "U1") (pin "18") (pinfunction "VSS_18") (pintype "power_in"))
      (node (ref "U1") (pin "28") (pinfunction "PB2_28") (pintype "bidirectional"))
      (node (ref "U1") (pin "63") (pinfunction "VSS_63") (pintype "power_in"))
      (node (ref "U2") (pin "1") (pinfunction "GND_1") (pintype "power_in"))
      (node (ref "U2") (pin "EXP@1") (pinfunction "GND_EXP@1") (pintype "power_in"))
      (node (ref "U2") (pin "EXP@10") (pinfunction "GND_EXP@10") (pintype "power_in"))
      (node (ref "U2") (pin "EXP@11") (pinfunction "GND_EXP@11") (pintype "power_in"))
      (node (ref "U2") (pin "EXP@12") (pinfunction "GND_EXP@12") (pintype "power_in"))
      (node (ref "U2") (pin "EXP@13") (pinfunction "GND_EXP@13") (pintype "power_in"))
      (node (ref "U2") (pin "EXP@14") (pinfunction "GND_EXP@14") (pintype "power_in"))
      (node (ref "U2") (pin "EXP@15") (pinfunction "GND_EXP@15") (pintype "power_in"))
      (node (ref "U2") (pin "EXP@16") (pinfunction "GND_EXP@16") (pintype "power_in"))
      (node (ref "U2") (pin "EXP@2") (pinfunction "GND_EXP@2") (pintype "power_in"))
      (node (ref "U2") (pin "EXP@3") (pinfunction "GND_EXP@3") (pintype "power_in"))
      (node (ref "U2") (pin "EXP@4") (pinfunction "GND_EXP@4") (pintype "power_in"))
      (node (ref "U2") (pin "EXP@5") (pinfunction "GND_EXP@5") (pintype "power_in"))
      (node (ref "U2") (pin "EXP@6") (pinfunction "GND_EXP@6") (pintype "power_in"))
      (node (ref "U2") (pin "EXP@7") (pinfunction "GND_EXP@7") (pintype "power_in"))
      (node (ref "U2") (pin "EXP@8") (pinfunction "GND_EXP@8") (pintype "power_in"))
      (node (ref "U2") (pin "EXP@9") (pinfunction "GND_EXP@9") (pintype "power_in"))
      (node (ref "U3") (pin "2") (pinfunction "GND_2") (pintype "passive"))
      (node (ref "U3") (pin "5") (pinfunction "GND_5") (pintype "passive"))
      (node (ref "U3") (pin "6") (pinfunction "GND_6") (pintype "passive"))
      (node (ref "U4") (pin "13") (pinfunction "MTDO_13") (pintype "bidirectional"))
      (node (ref "U4") (pin "EXP@1") (pinfunction "GND_EXP@1") (pintype "power_in"))
      (node (ref "U4") (pin "EXP@10") (pinfunction "GND_EXP@10") (pintype "power_in"))
      (node (ref "U4") (pin "EXP@11") (pinfunction "GND_EXP@11") (pintype "power_in"))
      (node (ref "U4") (pin "EXP@2") (pinfunction "GND_EXP@2") (pintype "power_in"))
      (node (ref "U4") (pin "EXP@3") (pinfunction "GND_EXP@3") (pintype "power_in"))
      (node (ref "U4") (pin "EXP@5") (pinfunction "GND_EXP@5") (pintype "power_in"))
      (node (ref "U4") (pin "EXP@6") (pinfunction "GND_EXP@6") (pintype "power_in"))
      (node (ref "U4") (pin "EXP@7") (pinfunction "GND_EXP@7") (pintype "power_in"))
      (node (ref "U4") (pin "EXP@9") (pinfunction "GND_EXP@9") (pintype "power_in"))
      (node (ref "U5") (pin "4") (pinfunction "GND_4") (pintype "bidirectional"))
      (node (ref "U6") (pin "12") (pinfunction "SDO2_12") (pintype "output"))
      (node (ref "U6") (pin "17") (pinfunction "SDO1_17") (pintype "output"))
      (node (ref "U6") (pin "20") (pinfunction "CSB3_20") (pintype "input"))
      (node (ref "U6") (pin "4") (pinfunction "GNDA_4") (pintype "power_in"))
      (node (ref "U6") (pin "6") (pinfunction "GNDIO_6") (pintype "power_in"))
      (node (ref "U7") (pin "2") (pinfunction "VSS_2") (pintype "power_in"))
      (node (ref "U8") (pin "2") (pinfunction "GND_2") (pintype "power_in"))
      (node (ref "U8") (pin "4") (pinfunction "GND_4") (pintype "power_in"))
      (node (ref "U9") (pin "1") (pinfunction "GND_1") (pintype "power_in"))
      (node (ref "Y1") (pin "2") (pinfunction "2_2") (pintype "passive"))
      (node (ref "Y1") (pin "4") (pinfunction "4_4") (pintype "passive"))
      (node (ref "Y2") (pin "2") (pinfunction "2_2") (pintype "passive"))
      (node (ref "Y2") (pin "4") (pinfunction "4_4") (pintype "passive"))
      (node (ref "Y4") (pin "2") (pinfunction "2_2") (pintype "passive"))
      (node (ref "Y4") (pin "4") (pinfunction "4_4") (pintype "passive"))
    )
    (net (code "38") (name "LED_B") (class "Default")
      (node (ref "R10") (pin "1") (pinfunction "1_1") (pintype "passive"))
      (node (ref "U1") (pin "56") (pinfunction "PB4_56") (pintype "bidirectional"))
    )
    (net (code "39") (name "LED_G") (class "Default")
      (node (ref "R9") (pin "1") (pinfunction "1_1") (pintype "passive"))
      (node (ref "U1") (pin "57") (pinfunction "PB5_57") (pintype "bidirectional"))
    )
    (net (code "40") (name "LED_R") (class "Default")
      (node (ref "R8") (pin "1") (pinfunction "1_1") (pintype "passive"))
      (node (ref "U1") (pin "26") (pinfunction "PB0_26") (pintype "bidirectional"))
    )
    (net (code "41") (name "NRST") (class "Default")
      (node (ref "C28") (pin "1") (pinfunction "1_1") (pintype "passive"))
      (node (ref "Q2") (pin "1") (pinfunction "G_1") (pintype "passive"))
      (node (ref "R12") (pin "1") (pinfunction "1_1") (pintype "passive"))
      (node (ref "RESET/BOOT") (pin "1") (pinfunction "1_1") (pintype "passive"))
      (node (ref "SWD") (pin "2") (pinfunction "2_2") (pintype "passive"))
      (node (ref "U1") (pin "7") (pinfunction "NRST_7") (pintype "bidirectional"))
    )
    (net (code "42") (name "Net-(C19-Pad1)") (class "Default")
      (node (ref "C19") (pin "1") (pinfunction "1_1") (pintype "passive"))
      (node (ref "U$1") (pin "ANT") (pinfunction "ANT_ANT") (pintype "passive"))
    )
    (net (code "43") (name "Net-(LED-KBLUE)") (class "Default")
      (node (ref "LED") (pin "3") (pinfunction "KBLUE_3") (pintype "passive"))
      (node (ref "R10") (pin "2") (pinfunction "2_2") (pintype "passive"))
    )
    (net (code "44") (name "Net-(LED-KGREEN)") (class "Default")
      (node (ref "LED") (pin "2") (pinfunction "KGREEN_2") (pintype "passive"))
      (node (ref "R9") (pin "2") (pinfunction "2_2") (pintype "passive"))
    )
    (net (code "45") (name "Net-(LED-KRED)") (class "Default")
      (node (ref "LED") (pin "1") (pinfunction "KRED_1") (pintype "passive"))
      (node (ref "R8") (pin "2") (pinfunction "2_2") (pintype "passive"))
    )
    (net (code "46") (name "Net-(ON-PadA)") (class "Default")
      (node (ref "ON") (pin "A") (pinfunction "A_A") (pintype "passive"))
      (node (ref "R11") (pin "1") (pinfunction "1_1") (pintype "passive"))
    )
    (net (code "47") (name "Net-(Q1-G)") (class "Default")
      (node (ref "Q1") (pin "1") (pinfunction "G_1") (pintype "passive"))
      (node (ref "R16") (pin "1") (pinfunction "1_1") (pintype "passive"))
      (node (ref "R17") (pin "2") (pinfunction "2_2") (pintype "passive"))
    )
    (net (code "48") (name "Net-(Q2-D)") (class "Default")
      (node (ref "Q2") (pin "3") (pinfunction "D_3") (pintype "passive"))
      (node (ref "R13") (pin "1") (pinfunction "1_1") (pintype "passive"))
      (node (ref "R14") (pin "1") (pinfunction "1_1") (pintype "passive"))
    )
    (net (code "49") (name "Net-(Q3-G)") (class "Default")
      (node (ref "Q3") (pin "1") (pinfunction "G_1") (pintype "passive"))
      (node (ref "R21") (pin "2") (pinfunction "2_2") (pintype "passive"))
      (node (ref "R22") (pin "1") (pinfunction "1_1") (pintype "passive"))
    )
    (net (code "50") (name "Net-(Q3-S)") (class "Default")
      (node (ref "D1") (pin "C") (pinfunction "C_C") (pintype "passive"))
      (node (ref "Q3") (pin "2") (pinfunction "S_2") (pintype "passive"))
      (node (ref "U8") (pin "1") (pinfunction "VIN_1") (pintype "input"))
    )
    (net (code "51") (name "Net-(U1A-OSC_IN)") (class "Default")
      (node (ref "C2") (pin "2") (pinfunction "2_2") (pintype "passive"))
      (node (ref "U1") (pin "5") (pinfunction "OSC_IN_5") (pintype "bidirectional"))
      (node (ref "Y1") (pin "1") (pinfunction "1_1") (pintype "passive"))
    )
    (net (code "52") (name "Net-(U1A-OSC_OUT)") (class "Default")
      (node (ref "C3") (pin "2") (pinfunction "2_2") (pintype "passive"))
      (node (ref "U1") (pin "6") (pinfunction "OSC_OUT_6") (pintype "bidirectional"))
      (node (ref "Y1") (pin "3") (pinfunction "3_3") (pintype "passive"))
    )
    (net (code "53") (name "Net-(U1A-VCAP1)") (class "Default")
      (node (ref "C8") (pin "1") (pinfunction "1_1") (pintype "passive"))
      (node (ref "U1") (pin "31") (pinfunction "VCAP1_31") (pintype "power_in"))
    )
    (net (code "54") (name "Net-(U1A-VCAP2)") (class "Default")
      (node (ref "C9") (pin "1") (pinfunction "1_1") (pintype "passive"))
      (node (ref "U1") (pin "47") (pinfunction "VCAP2_47") (pintype "power_in"))
    )
    (net (code "55") (name "Net-(U1A-VDDA)") (class "Default")
      (node (ref "C1") (pin "1") (pinfunction "1_1") (pintype "passive"))
      (node (ref "L1") (pin "1") (pinfunction "1_1") (pintype "passive"))
      (node (ref "U1") (pin "13") (pinfunction "VDDA_13") (pintype "power_in"))
    )
    (net (code "56") (name "Net-(U2-DCOUPL)") (class "Default")
      (node (ref "C12") (pin "1") (pinfunction "1_1") (pintype "passive"))
      (node (ref "U2") (pin "40") (pinfunction "DCOUPL_40") (pintype "power_in"))
    )
    (net (code "57") (name "Net-(U2-P2_1{slash}DD)") (class "Default")
      (node (ref "R4") (pin "2") (pinfunction "2_2") (pintype "passive"))
      (node (ref "U2") (pin "35") (pinfunction "P2_1/DD_35") (pintype "bidirectional"))
    )
    (net (code "58") (name "Net-(U2-P2_2{slash}DC)") (class "Default")
      (node (ref "R3") (pin "2") (pinfunction "2_2") (pintype "passive"))
      (node (ref "U2") (pin "34") (pinfunction "P2_2/DC_34") (pintype "bidirectional"))
    )
    (net (code "59") (name "Net-(U2-P2_3{slash}OSC32K_Q2)") (class "Default")
      (node (ref "C14") (pin "1") (pinfunction "1_1") (pintype "passive"))
      (node (ref "U2") (pin "33") (pinfunction "P2_3/OSC32K_Q2_33") (pintype "bidirectional"))
      (node (ref "Y3") (pin "2") (pinfunction "2_2") (pintype "passive"))
    )
    (net (code "60") (name "Net-(U2-P2_4{slash}OSC32K_Q1)") (class "Default")
      (node (ref "C13") (pin "1") (pinfunction "1_1") (pintype "passive"))
      (node (ref "U2") (pin "32") (pinfunction "P2_4/OSC32K_Q1_32") (pintype "bidirectional"))
      (node (ref "Y3") (pin "1") (pinfunction "1_1") (pintype "passive"))
    )
    (net (code "61") (name "Net-(U2-RBIAS)") (class "Default")
      (node (ref "R2") (pin "2") (pinfunction "2_2") (pintype "passive"))
      (node (ref "U2") (pin "30") (pinfunction "RBIAS_30") (pintype "bidirectional"))
    )
    (net (code "62") (name "Net-(U2-RESET_N)") (class "Default")
      (node (ref "R1") (pin "1") (pinfunction "1_1") (pintype "passive"))
      (node (ref "U2") (pin "20") (pinfunction "RESET_N_20") (pintype "input"))
    )
    (net (code "63") (name "Net-(U2-RF_N)") (class "Default")
      (node (ref "U2") (pin "26") (pinfunction "RF_N_26") (pintype "bidirectional"))
      (node (ref "U3") (pin "3") (pinfunction "BAL_3") (pintype "passive"))
    )
    (net (code "64") (name "Net-(U2-RF_P)") (class "Default")
      (node (ref "U2") (pin "25") (pinfunction "RF_P_25") (pintype "bidirectional"))
      (node (ref "U3") (pin "4") (pinfunction "BAL_4") (pintype "passive"))
    )
    (net (code "65") (name "Net-(U2-XOSC_Q1)") (class "Default")
      (node (ref "C10") (pin "2") (pinfunction "2_2") (pintype "passive"))
      (node (ref "U2") (pin "22") (pinfunction "XOSC_Q1_22") (pintype "bidirectional"))
      (node (ref "Y2") (pin "1") (pinfunction "1_1") (pintype "passive"))
    )
    (net (code "66") (name "Net-(U2-XOSC_Q2)") (class "Default")
      (node (ref "C11") (pin "2") (pinfunction "2_2") (pintype "passive"))
      (node (ref "U2") (pin "23") (pinfunction "XOSC_Q2_23") (pintype "bidirectional"))
      (node (ref "Y2") (pin "3") (pinfunction "3_3") (pintype "passive"))
    )
    (net (code "67") (name "Net-(U3-UNBAL)") (class "Default")
      (node (ref "U$2") (pin "ANT") (pinfunction "ANT_ANT") (pintype "passive"))
      (node (ref "U3") (pin "1") (pinfunction "UNBAL_1") (pintype "passive"))
    )
    (net (code "68") (name "Net-(U4-LNA)") (class "Default")
      (node (ref "C19") (pin "2") (pinfunction "2_2") (pintype "passive"))
      (node (ref "U4") (pin "2") (pinfunction "LNA_2") (pintype "bidirectional"))
    )
    (net (code "69") (name "Net-(U4-RES12K)") (class "Default")
      (node (ref "R5") (pin "1") (pinfunction "1_1") (pintype "passive"))
      (node (ref "U4") (pin "31") (pinfunction "RES12K_31") (pintype "input"))
    )
    (net (code "70") (name "Net-(U4-XTAL_IN)") (class "Default")
      (node (ref "C20") (pin "1") (pinfunction "1_1") (pintype "passive"))
      (node (ref "U4") (pin "28") (pinfunction "XTAL_IN_28") (pintype "bidirectional"))
      (node (ref "Y4") (pin "3") (pinfunction "3_3") (pintype "passive"))
    )
    (net (code "71") (name "Net-(U4-XTAL_OUT)") (class "Default")
      (node (ref "C21") (pin "1") (pinfunction "1_1") (pintype "passive"))
      (node (ref "U4") (pin "27") (pinfunction "XTAL_OUT_27") (pintype "bidirectional"))
      (node (ref "Y4") (pin "1") (pinfunction "1_1") (pintype "passive"))
    )
    (net (code "72") (name "Net-(U7-PROG)") (class "Default")
      (node (ref "R20") (pin "2") (pinfunction "2_2") (pintype "passive"))
      (node (ref "U7") (pin "5") (pinfunction "PROG_5") (pintype "input"))
    )
    (net (code "73") (name "SCL") (class "Default")
      (node (ref "R6") (pin "1") (pinfunction "1_1") (pintype "passive"))
      (node (ref "U1") (pin "29") (pinfunction "PB10_29") (pintype "bidirectional"))
      (node (ref "U6") (pin "9") (pinfunction "SCX_9") (pintype "input"))
    )
    (net (code "74") (name "SDA") (class "Default")
      (node (ref "R7") (pin "1") (pinfunction "1_1") (pintype "passive"))
      (node (ref "U1") (pin "30") (pinfunction "PB11_30") (pintype "bidirectional"))
      (node (ref "U6") (pin "11") (pinfunction "SDX_11") (pintype "bidirectional"))
    )
    (net (code "75") (name "SD_CLK") (class "Default")
      (node (ref "U4") (pin "21") (pinfunction "SD_CLK_21") (pintype "bidirectional"))
      (node (ref "U5") (pin "6") (pinfunction "SCK_6") (pintype "bidirectional"))
    )
    (net (code "76") (name "SD_CMD") (class "Default")
      (node (ref "U4") (pin "20") (pinfunction "SD_CMD_20") (pintype "bidirectional"))
      (node (ref "U5") (pin "1") (pinfunction "CS_1") (pintype "bidirectional"))
    )
    (net (code "77") (name "SD_D0") (class "Default")
      (node (ref "U4") (pin "22") (pinfunction "SD_DATA_0_22") (pintype "bidirectional"))
      (node (ref "U5") (pin "2") (pinfunction "MISO_2") (pintype "bidirectional"))
    )
    (net (code "78") (name "SD_D1") (class "Default")
      (node (ref "U4") (pin "23") (pinfunction "SD_DATA_1_23") (pintype "bidirectional"))
      (node (ref "U5") (pin "5") (pinfunction "MOSI_5") (pintype "bidirectional"))
    )
    (net (code "79") (name "SD_D2") (class "Default")
      (node (ref "U4") (pin "18") (pinfunction "SD_DATA_2_18") (pintype "bidirectional"))
      (node (ref "U5") (pin "7") (pinfunction "HOLD_7") (pintype "bidirectional"))
    )
    (net (code "80") (name "SD_D3") (class "Default")
      (node (ref "U4") (pin "19") (pinfunction "SD_DATA_3_19") (pintype "bidirectional"))
      (node (ref "U5") (pin "3") (pinfunction "WP_3") (pintype "bidirectional"))
    )
    (net (code "81") (name "SW1") (class "Default")
      (node (ref "R15") (pin "2") (pinfunction "2_2") (pintype "passive"))
      (node (ref "U1") (pin "2") (pinfunction "PC13_2") (pintype "bidirectional"))
      (node (ref "USER") (pin "2") (pinfunction "2_2") (pintype "passive"))
    )
    (net (code "82") (name "SWCLK") (class "Default")
      (node (ref "SWD") (pin "4") (pinfunction "4_4") (pintype "passive"))
      (node (ref "U1") (pin "49") (pinfunction "PA14_49") (pintype "bidirectional"))
    )
    (net (code "83") (name "SWDIO") (class "Default")
      (node (ref "SWD") (pin "3") (pinfunction "3_3") (pintype "passive"))
      (node (ref "U1") (pin "46") (pinfunction "PA13_46") (pintype "bidirectional"))
    )
    (net (code "84") (name "USB_DM") (class "Default")
      (node (ref "J1") (pin "2") (pinfunction "D-_2") (pintype "bidirectional"))
      (node (ref "U1") (pin "44") (pinfunction "PA11_44") (pintype "bidirectional"))
    )
    (net (code "85") (name "USB_DP") (class "Default")
      (node (ref "J1") (pin "3") (pinfunction "D+_3") (pintype "bidirectional"))
      (node (ref "U1") (pin "45") (pinfunction "PA12_45") (pintype "bidirectional"))
    )
    (net (code "86") (name "VBUS") (class "Default")
      (node (ref "J1") (pin "1") (pinfunction "VBUS_1") (pintype "power_in"))
      (node (ref "Q1") (pin "3") (pinfunction "D_3") (pintype "passive"))
      (node (ref "U1") (pin "42") (pinfunction "PA9_42") (pintype "bidirectional"))
    )
    (net (code "87") (name "VIN") (class "Default")
      (node (ref "C33") (pin "+") (pinfunction "+_+") (pintype "passive"))
      (node (ref "EXT-1") (pin "2") (pinfunction "2_2") (pintype "passive"))
      (node (ref "R16") (pin "2") (pinfunction "2_2") (pintype "passive"))
      (node (ref "U9") (pin "3") (pinfunction "VIN_3") (pintype "input"))
    )
    (net (code "88") (name "V_BAT") (class "Default")
      (node (ref "C30") (pin "1") (pinfunction "1_1") (pintype "passive"))
      (node (ref "EXT-2") (pin "2") (pinfunction "2_2") (pintype "passive"))
      (node (ref "J2") (pin "+") (pinfunction "+_+") (pintype "passive"))
      (node (ref "Q3") (pin "3") (pinfunction "D_3") (pintype "passive"))
      (node (ref "R18") (pin "2") (pinfunction "2_2") (pintype "passive"))
      (node (ref "U7") (pin "3") (pinfunction "VBAT_3") (pintype "bidirectional"))
    )
    (net (code "89") (name "WIFI_MODE") (class "Default")
      (node (ref "U1") (pin "34") (pinfunction "PB13_34") (pintype "bidirectional"))
      (node (ref "U4") (pin "15") (pinfunction "GPIO0_15") (pintype "bidirectional"))
    )
    (net (code "90") (name "WIFI_PWD") (class "Default")
      (node (ref "U1") (pin "33") (pinfunction "PB12_33") (pintype "bidirectional"))
      (node (ref "U4") (pin "7") (pinfunction "CHIP_EN_7") (pintype "input"))
    )
    (net (code "91") (name "WIFI_RST") (class "Default")
      (node (ref "U1") (pin "3") (pinfunction "PC14_3") (pintype "bidirectional"))
      (node (ref "U4") (pin "32") (pinfunction "EXT_RSTB_32") (pintype "input"))
    )
    (net (code "92") (name "WIFI_RX") (class "Default")
      (node (ref "U1") (pin "15") (pinfunction "PA1_15") (pintype "bidirectional"))
      (node (ref "U4") (pin "26") (pinfunction "U0TXD_26") (pintype "bidirectional"))
    )
    (net (code "93") (name "WIFI_TX") (class "Default")
      (node (ref "U1") (pin "14") (pinfunction "PA0-WKUP_14") (pintype "bidirectional"))
      (node (ref "U4") (pin "25") (pinfunction "U0RXD_25") (pintype "bidirectional"))
    )
    (net (code "94") (name "unconnected-(J1-ID-Pad4)") (class "Default")
      (node (ref "J1") (pin "4") (pinfunction "ID_4") (pintype "bidirectional"))
    )
    (net (code "95") (name "unconnected-(U2-P0_0-Pad19)") (class "Default")
      (node (ref "U2") (pin "19") (pinfunction "P0_0_19") (pintype "bidirectional"))
    )
    (net (code "96") (name "unconnected-(U2-P0_1-Pad18)") (class "Default")
      (node (ref "U2") (pin "18") (pinfunction "P0_1_18") (pintype "bidirectional"))
    )
    (net (code "97") (name "unconnected-(U2-P0_2-Pad17)") (class "Default")
      (node (ref "U2") (pin "17") (pinfunction "P0_2_17") (pintype "bidirectional"))
    )
    (net (code "98") (name "unconnected-(U2-P0_3-Pad16)") (class "Default")
      (node (ref "U2") (pin "16") (pinfunction "P0_3_16") (pintype "bidirectional"))
    )
    (net (code "99") (name "unconnected-(U2-P0_4-Pad15)") (class "Default")
      (node (ref "U2") (pin "15") (pinfunction "P0_4_15") (pintype "bidirectional"))
    )
    (net (code "100") (name "unconnected-(U2-P0_5-Pad14)") (class "Default")
      (node (ref "U2") (pin "14") (pinfunction "P0_5_14") (pintype "bidirectional"))
    )
    (net (code "101") (name "unconnected-(U2-P0_6-Pad13)") (class "Default")
      (node (ref "U2") (pin "13") (pinfunction "P0_6_13") (pintype "bidirectional"))
    )
    (net (code "102") (name "unconnected-(U2-P0_7-Pad12)") (class "Default")
      (node (ref "U2") (pin "12") (pinfunction "P0_7_12") (pintype "bidirectional"))
    )
    (net (code "103") (name "unconnected-(U2-P1_0-Pad11)") (class "Default")
      (node (ref "U2") (pin "11") (pinfunction "P1_0_11") (pintype "bidirectional"))
    )
    (net (code "104") (name "unconnected-(U2-P1_1-Pad9)") (class "Default")
      (node (ref "U2") (pin "9") (pinfunction "P1_1_9") (pintype "bidirectional"))
    )
    (net (code "105") (name "unconnected-(U2-P1_2-Pad8)") (class "Default")
      (node (ref "U2") (pin "8") (pinfunction "P1_2_8") (pintype "bidirectional"))
    )
    (net (code "106") (name "unconnected-(U2-P1_3-Pad7)") (class "Default")
      (node (ref "U2") (pin "7") (pinfunction "P1_3_7") (pintype "bidirectional"))
    )
    (net (code "107") (name "unconnected-(U2-P1_4-Pad6)") (class "Default")
      (node (ref "U2") (pin "6") (pinfunction "P1_4_6") (pintype "bidirectional"))
    )
    (net (code "108") (name "unconnected-(U2-P1_5-Pad5)") (class "Default")
      (node (ref "U2") (pin "5") (pinfunction "P1_5_5") (pintype "bidirectional"))
    )
    (net (code "109") (name "unconnected-(U2-P2_0-Pad36)") (class "Default")
      (node (ref "U2") (pin "36") (pinfunction "P2_0_36") (pintype "bidirectional"))
    )
    (net (code "110") (name "unconnected-(U2-SCL-Pad2)") (class "Default")
      (node (ref "U2") (pin "2") (pinfunction "SCL_2") (pintype "bidirectional"))
    )
    (net (code "111") (name "unconnected-(U2-SDA-Pad3)") (class "Default")
      (node (ref "U2") (pin "3") (pinfunction "SDA_3") (pintype "bidirectional"))
    )
    (net (code "112") (name "unconnected-(U4-GPIO4-Pad16)") (class "Default")
      (node (ref "U4") (pin "16") (pinfunction "GPIO4_16") (pintype "bidirectional"))
    )
    (net (code "113") (name "unconnected-(U4-GPIO5-Pad24)") (class "Default")
      (node (ref "U4") (pin "24") (pinfunction "GPIO5_24") (pintype "bidirectional"))
    )
    (net (code "114") (name "unconnected-(U4-MTCK-Pad12)") (class "Default")
      (node (ref "U4") (pin "12") (pinfunction "MTCK_12") (pintype "bidirectional"))
    )
    (net (code "115") (name "unconnected-(U4-MTDI-Pad10)") (class "Default")
      (node (ref "U4") (pin "10") (pinfunction "MTDI_10") (pintype "bidirectional"))
    )
    (net (code "116") (name "unconnected-(U4-MTMS-Pad9)") (class "Default")
      (node (ref "U4") (pin "9") (pinfunction "MTMS_9") (pintype "bidirectional"))
    )
    (net (code "117") (name "unconnected-(U4-TOUT-Pad6)") (class "Default")
      (node (ref "U4") (pin "6") (pinfunction "TOUT_6") (pintype "input"))
    )
    (net (code "118") (name "unconnected-(U4-XPD_DCDC-Pad8)") (class "Default")
      (node (ref "U4") (pin "8") (pinfunction "XPD_DCDC_8") (pintype "bidirectional"))
    )
    (net (code "119") (name "unconnected-(U6-CSB1-Pad16)") (class "Default")
      (node (ref "U6") (pin "16") (pinfunction "CSB1_16") (pintype "input"))
    )
    (net (code "120") (name "unconnected-(U6-CSB2-Pad5)") (class "Default")
      (node (ref "U6") (pin "5") (pinfunction "CSB2_5") (pintype "input"))
    )
    (net (code "121") (name "unconnected-(U6-DRDYM-Pad2)") (class "Default")
      (node (ref "U6") (pin "2") (pinfunction "DRDYM_2") (pintype "output"))
    )
    (net (code "122") (name "unconnected-(U6-INT1-Pad19)") (class "Default")
      (node (ref "U6") (pin "19") (pinfunction "INT1_19") (pintype "output"))
    )
    (net (code "123") (name "unconnected-(U6-INT2-Pad1)") (class "Default")
      (node (ref "U6") (pin "1") (pinfunction "INT2_1") (pintype "output"))
    )
    (net (code "124") (name "unconnected-(U6-INT3-Pad14)") (class "Default")
      (node (ref "U6") (pin "14") (pinfunction "INT3_14") (pintype "output"))
    )
    (net (code "125") (name "unconnected-(U6-INT4-Pad15)") (class "Default")
      (node (ref "U6") (pin "15") (pinfunction "INT4_15") (pintype "output"))
    )
    (net (code "126") (name "unconnected-(U6-INT5-Pad10)") (class "Default")
      (node (ref "U6") (pin "10") (pinfunction "INT5_10") (pintype "output"))
    )
    (net (code "127") (name "unconnected-(U7-STAT-Pad1)") (class "Default")
      (node (ref "U7") (pin "1") (pinfunction "STAT_1") (pintype "output"))
    )
  )
)
